# LCD_Board.net
KiCad netlist of a schematic drawn in EAGLE
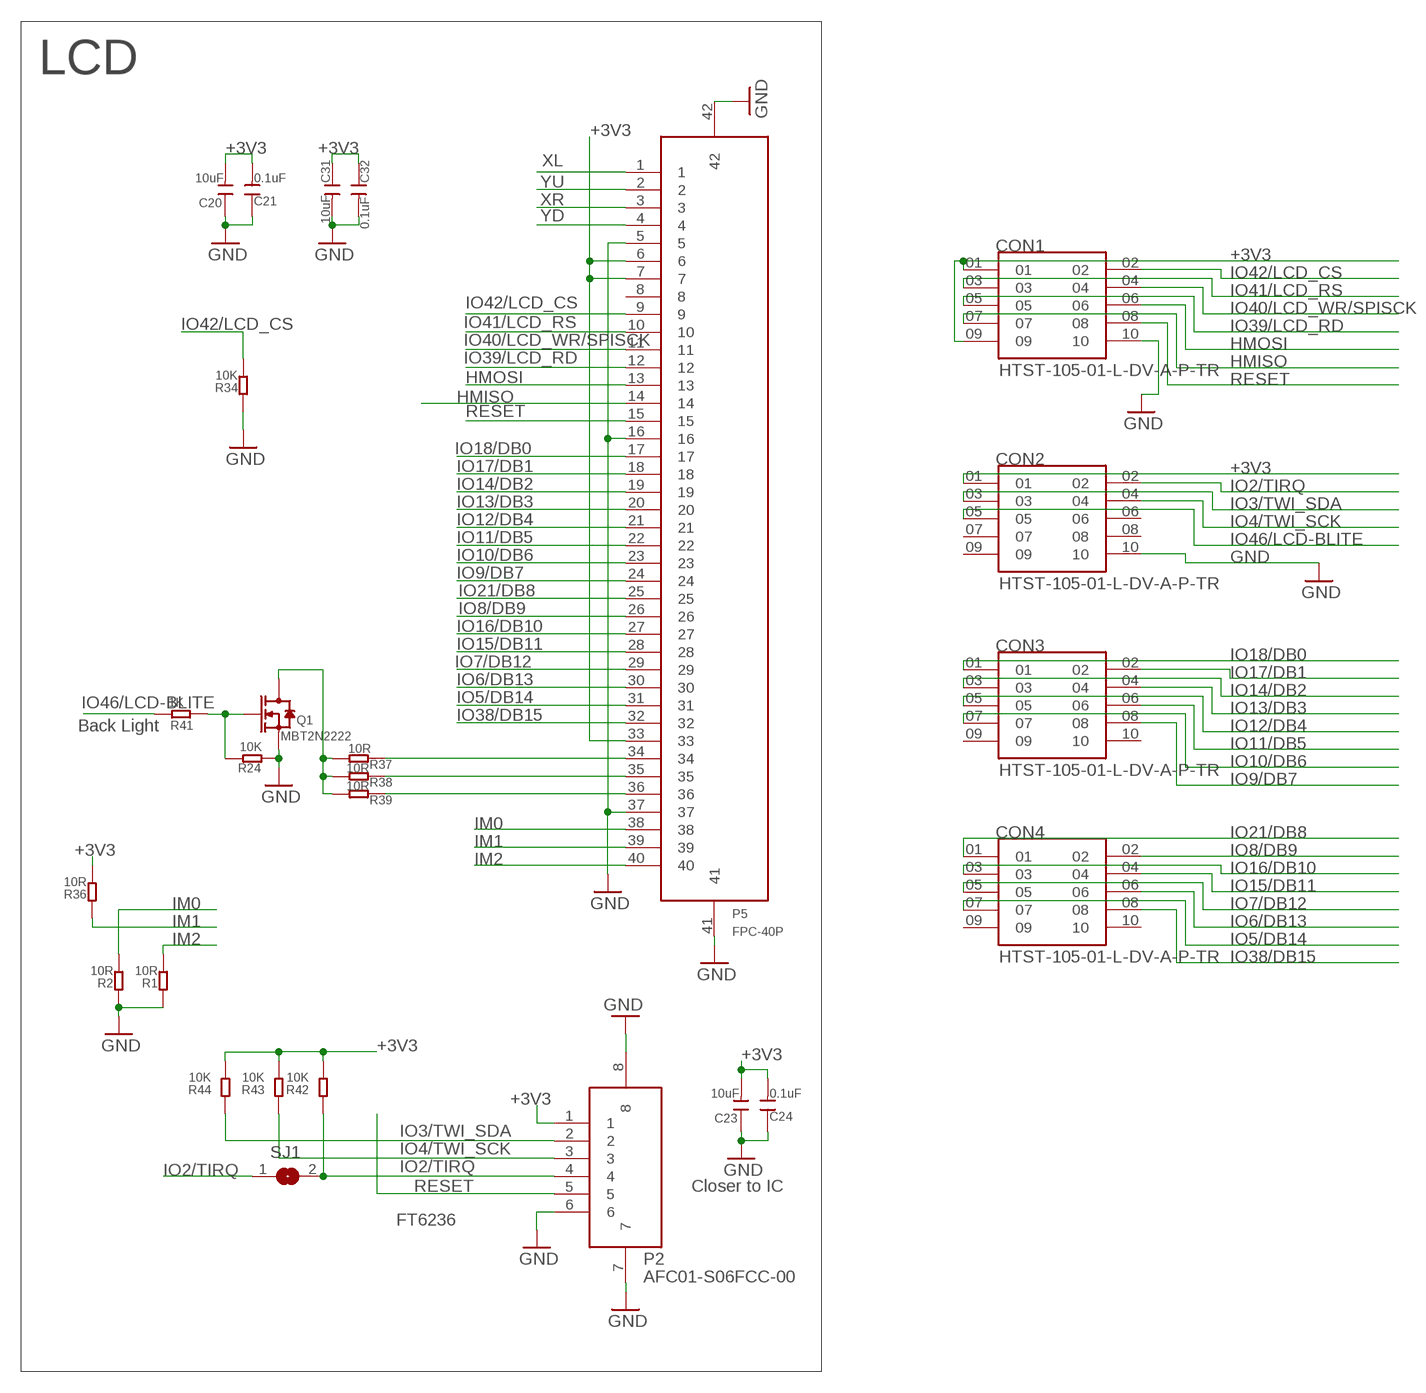
[diagram p0: schematic, sheet 1]

(export (version "E")
  (design (tool "Eeschema 10.0.6"))
  (components
    (comp (ref "C20")
      (value "10uF")
      (footprint "eagle-import:DISCRETE_C1206")
      (libsource (lib "eagle-import") (part "DISCRETE_C-1206"))
    )
    (comp (ref "C21")
      (value "0.1uF")
      (footprint "eagle-import:DISCRETE_C0603")
      (libsource (lib "eagle-import") (part "DISCRETE_C-0603"))
    )
    (comp (ref "C23")
      (value "10uF")
      (footprint "eagle-import:DISCRETE_C1206")
      (libsource (lib "eagle-import") (part "DISCRETE_C-1206"))
    )
    (comp (ref "C24")
      (value "0.1uF")
      (footprint "eagle-import:DISCRETE_C0603")
      (libsource (lib "eagle-import") (part "DISCRETE_C-0603"))
    )
    (comp (ref "C31")
      (value "10uF")
      (footprint "eagle-import:DISCRETE_C1206")
      (libsource (lib "eagle-import") (part "DISCRETE_C-1206"))
    )
    (comp (ref "C32")
      (value "0.1uF")
      (footprint "eagle-import:DISCRETE_C0603")
      (libsource (lib "eagle-import") (part "DISCRETE_C-0603"))
    )
    (comp (ref "CON1")
      (value "HTST-105-01-L-DV-A-P-TR")
      (footprint "eagle-import:SAMTEC_HTST-105-01-L-DV-A-P-TR")
      (fields (field (name "MF") "Samtec") (field (name "MP") "HTST-105-01-L-DV-A-P"))
      (libsource (lib "eagle-import") (part "HTST-105-01-L-DV-A-P-TR"))
    )
    (comp (ref "CON2")
      (value "HTST-105-01-L-DV-A-P-TR")
      (footprint "eagle-import:SAMTEC_HTST-105-01-L-DV-A-P-TR")
      (fields (field (name "MF") "Samtec") (field (name "MP") "HTST-105-01-L-DV-A-P"))
      (libsource (lib "eagle-import") (part "HTST-105-01-L-DV-A-P-TR"))
    )
    (comp (ref "CON3")
      (value "HTST-105-01-L-DV-A-P-TR")
      (footprint "eagle-import:SAMTEC_HTST-105-01-L-DV-A-P-TR")
      (fields (field (name "MF") "Samtec") (field (name "MP") "HTST-105-01-L-DV-A-P"))
      (libsource (lib "eagle-import") (part "HTST-105-01-L-DV-A-P-TR"))
    )
    (comp (ref "CON4")
      (value "HTST-105-01-L-DV-A-P-TR")
      (footprint "eagle-import:SAMTEC_HTST-105-01-L-DV-A-P-TR")
      (fields (field (name "MF") "Samtec") (field (name "MP") "HTST-105-01-L-DV-A-P"))
      (libsource (lib "eagle-import") (part "HTST-105-01-L-DV-A-P-TR"))
    )
    (comp (ref "P2")
      (value "AFC01-S06FCC-00")
      (footprint "eagle-import:SMD8-50P-740L535W")
      (libsource (lib "eagle-import") (part "AFC01-S06FCC-00"))
    )
    (comp (ref "P5")
      (value "FPC-40P")
      (footprint "eagle-import:SMD42-50P-2560L490W")
      (libsource (lib "eagle-import") (part "FPC-40P"))
    )
    (comp (ref "Q1")
      (value "MBT2N2222")
      (footprint "eagle-import:SOT23@1")
      (libsource (lib "eagle-import") (part "MOSFET-N'SOT23'"))
    )
    (comp (ref "R1")
      (value "10R")
      (footprint "eagle-import:DISCRETE_R0603")
      (libsource (lib "eagle-import") (part "DISCRETE_R-0603"))
    )
    (comp (ref "R2")
      (value "10R")
      (footprint "eagle-import:DISCRETE_R0603")
      (libsource (lib "eagle-import") (part "DISCRETE_R-0603"))
    )
    (comp (ref "R24")
      (value "10K")
      (footprint "eagle-import:DISCRETE_R0603")
      (libsource (lib "eagle-import") (part "DISCRETE_R-0603"))
    )
    (comp (ref "R34")
      (value "10K")
      (footprint "eagle-import:DISCRETE_R0603")
      (libsource (lib "eagle-import") (part "DISCRETE_R-0603"))
    )
    (comp (ref "R36")
      (value "10R")
      (footprint "eagle-import:DISCRETE_R0603")
      (libsource (lib "eagle-import") (part "DISCRETE_R-0603"))
    )
    (comp (ref "R37")
      (value "10R")
      (footprint "eagle-import:DISCRETE_R0603")
      (libsource (lib "eagle-import") (part "DISCRETE_R-0603"))
    )
    (comp (ref "R38")
      (value "10R")
      (footprint "eagle-import:DISCRETE_R0603")
      (libsource (lib "eagle-import") (part "DISCRETE_R-0603"))
    )
    (comp (ref "R39")
      (value "10R")
      (footprint "eagle-import:DISCRETE_R0603")
      (libsource (lib "eagle-import") (part "DISCRETE_R-0603"))
    )
    (comp (ref "R41")
      (value "1K")
      (footprint "eagle-import:DISCRETE_R0603")
      (libsource (lib "eagle-import") (part "DISCRETE_R-0603"))
    )
    (comp (ref "R42")
      (value "10K")
      (footprint "eagle-import:DISCRETE_R0603")
      (libsource (lib "eagle-import") (part "DISCRETE_R-0603"))
    )
    (comp (ref "R43")
      (value "10K")
      (footprint "eagle-import:DISCRETE_R0603")
      (libsource (lib "eagle-import") (part "DISCRETE_R-0603"))
    )
    (comp (ref "R44")
      (value "10K")
      (footprint "eagle-import:DISCRETE_R0603")
      (libsource (lib "eagle-import") (part "DISCRETE_R-0603"))
    )
    (comp (ref "SJ1") (value "SJ") (footprint "eagle-import:SJ") (libsource (lib "eagle-import") (part "SJ")))
  )
  (nets
    (net (code "1") (name "/+3V3") (class "Default")
      (node (ref "C20") (pin "2") (pinfunction "2_2") (pintype "passive"))
      (node (ref "C21") (pin "2") (pinfunction "2_2") (pintype "passive"))
      (node (ref "C23") (pin "2") (pinfunction "2_2") (pintype "passive"))
      (node (ref "C24") (pin "2") (pinfunction "2_2") (pintype "passive"))
      (node (ref "C31") (pin "1") (pinfunction "1_1") (pintype "passive"))
      (node (ref "C32") (pin "1") (pinfunction "1_1") (pintype "passive"))
      (node (ref "CON1") (pin "01") (pinfunction "01_01") (pintype "passive"))
      (node (ref "CON1") (pin "09") (pinfunction "09_09") (pintype "passive"))
      (node (ref "CON2") (pin "01") (pinfunction "01_01") (pintype "passive"))
      (node (ref "P2") (pin "1") (pinfunction "1_1") (pintype "bidirectional"))
      (node (ref "P5") (pin "33") (pinfunction "33_33") (pintype "bidirectional"))
      (node (ref "P5") (pin "6") (pinfunction "6_6") (pintype "bidirectional"))
      (node (ref "P5") (pin "7") (pinfunction "7_7") (pintype "bidirectional"))
      (node (ref "R36") (pin "2") (pinfunction "2_2") (pintype "passive"))
      (node (ref "R42") (pin "2") (pinfunction "2_2") (pintype "passive"))
      (node (ref "R43") (pin "2") (pinfunction "2_2") (pintype "passive"))
      (node (ref "R44") (pin "2") (pinfunction "2_2") (pintype "passive"))
    )
    (net (code "2") (name "/HMISO") (class "Default")
      (node (ref "CON1") (pin "07") (pinfunction "07_07") (pintype "passive"))
      (node (ref "P5") (pin "14") (pinfunction "14_14") (pintype "bidirectional"))
    )
    (net (code "3") (name "/HMOSI") (class "Default")
      (node (ref "CON1") (pin "06") (pinfunction "06_06") (pintype "passive"))
      (node (ref "P5") (pin "13") (pinfunction "13_13") (pintype "bidirectional"))
    )
    (net (code "4") (name "/IM0") (class "Default")
      (node (ref "P5") (pin "38") (pinfunction "38_38") (pintype "bidirectional"))
      (node (ref "R2") (pin "2") (pinfunction "2_2") (pintype "passive"))
    )
    (net (code "5") (name "/IM1") (class "Default")
      (node (ref "P5") (pin "39") (pinfunction "39_39") (pintype "bidirectional"))
      (node (ref "R36") (pin "1") (pinfunction "1_1") (pintype "passive"))
    )
    (net (code "6") (name "/IM2") (class "Default")
      (node (ref "P5") (pin "40") (pinfunction "40_40") (pintype "bidirectional"))
      (node (ref "R1") (pin "2") (pinfunction "2_2") (pintype "passive"))
    )
    (net (code "7") (name "/IO2{slash}TIRQ") (class "Default")
      (node (ref "CON2") (pin "02") (pinfunction "02_02") (pintype "passive"))
      (node (ref "P2") (pin "4") (pinfunction "4_4") (pintype "bidirectional"))
      (node (ref "R42") (pin "1") (pinfunction "1_1") (pintype "passive"))
      (node (ref "SJ1") (pin "1") (pinfunction "1_1") (pintype "passive"))
      (node (ref "SJ1") (pin "2") (pinfunction "2_2") (pintype "passive"))
    )
    (net (code "8") (name "/IO3{slash}TWI_SDA") (class "Default")
      (node (ref "CON2") (pin "03") (pinfunction "03_03") (pintype "passive"))
      (node (ref "P2") (pin "2") (pinfunction "2_2") (pintype "bidirectional"))
      (node (ref "R44") (pin "1") (pinfunction "1_1") (pintype "passive"))
    )
    (net (code "9") (name "/IO4{slash}TWI_SCK") (class "Default")
      (node (ref "CON2") (pin "04") (pinfunction "04_04") (pintype "passive"))
      (node (ref "P2") (pin "3") (pinfunction "3_3") (pintype "bidirectional"))
      (node (ref "R43") (pin "1") (pinfunction "1_1") (pintype "passive"))
    )
    (net (code "10") (name "/IO5{slash}DB14") (class "Default")
      (node (ref "CON4") (pin "07") (pinfunction "07_07") (pintype "passive"))
      (node (ref "P5") (pin "31") (pinfunction "31_31") (pintype "bidirectional"))
    )
    (net (code "11") (name "/IO6{slash}DB13") (class "Default")
      (node (ref "CON4") (pin "06") (pinfunction "06_06") (pintype "passive"))
      (node (ref "P5") (pin "30") (pinfunction "30_30") (pintype "bidirectional"))
    )
    (net (code "12") (name "/IO7{slash}DB12") (class "Default")
      (node (ref "CON4") (pin "05") (pinfunction "05_05") (pintype "passive"))
      (node (ref "P5") (pin "29") (pinfunction "29_29") (pintype "bidirectional"))
    )
    (net (code "13") (name "/IO8{slash}DB9") (class "Default")
      (node (ref "CON4") (pin "02") (pinfunction "02_02") (pintype "passive"))
      (node (ref "P5") (pin "26") (pinfunction "26_26") (pintype "bidirectional"))
    )
    (net (code "14") (name "/IO9{slash}DB7") (class "Default")
      (node (ref "CON3") (pin "08") (pinfunction "08_08") (pintype "passive"))
      (node (ref "P5") (pin "24") (pinfunction "24_24") (pintype "bidirectional"))
    )
    (net (code "15") (name "/IO10{slash}DB6") (class "Default")
      (node (ref "CON3") (pin "07") (pinfunction "07_07") (pintype "passive"))
      (node (ref "P5") (pin "23") (pinfunction "23_23") (pintype "bidirectional"))
    )
    (net (code "16") (name "/IO11{slash}DB5") (class "Default")
      (node (ref "CON3") (pin "06") (pinfunction "06_06") (pintype "passive"))
      (node (ref "P5") (pin "22") (pinfunction "22_22") (pintype "bidirectional"))
    )
    (net (code "17") (name "/IO12{slash}DB4") (class "Default")
      (node (ref "CON3") (pin "05") (pinfunction "05_05") (pintype "passive"))
      (node (ref "P5") (pin "21") (pinfunction "21_21") (pintype "bidirectional"))
    )
    (net (code "18") (name "/IO13{slash}DB3") (class "Default")
      (node (ref "CON3") (pin "04") (pinfunction "04_04") (pintype "passive"))
      (node (ref "P5") (pin "20") (pinfunction "20_20") (pintype "bidirectional"))
    )
    (net (code "19") (name "/IO14{slash}DB2") (class "Default")
      (node (ref "CON3") (pin "03") (pinfunction "03_03") (pintype "passive"))
      (node (ref "P5") (pin "19") (pinfunction "19_19") (pintype "bidirectional"))
    )
    (net (code "20") (name "/IO15{slash}DB11") (class "Default")
      (node (ref "CON4") (pin "04") (pinfunction "04_04") (pintype "passive"))
      (node (ref "P5") (pin "28") (pinfunction "28_28") (pintype "bidirectional"))
    )
    (net (code "21") (name "/IO16{slash}DB10") (class "Default")
      (node (ref "CON4") (pin "03") (pinfunction "03_03") (pintype "passive"))
      (node (ref "P5") (pin "27") (pinfunction "27_27") (pintype "bidirectional"))
    )
    (net (code "22") (name "/IO17{slash}DB1") (class "Default")
      (node (ref "CON3") (pin "02") (pinfunction "02_02") (pintype "passive"))
      (node (ref "P5") (pin "18") (pinfunction "18_18") (pintype "bidirectional"))
    )
    (net (code "23") (name "/IO18{slash}DB0") (class "Default")
      (node (ref "CON3") (pin "01") (pinfunction "01_01") (pintype "passive"))
      (node (ref "P5") (pin "17") (pinfunction "17_17") (pintype "bidirectional"))
    )
    (net (code "24") (name "/IO21{slash}DB8") (class "Default")
      (node (ref "CON4") (pin "01") (pinfunction "01_01") (pintype "passive"))
      (node (ref "P5") (pin "25") (pinfunction "25_25") (pintype "bidirectional"))
    )
    (net (code "25") (name "/IO38{slash}DB15") (class "Default")
      (node (ref "CON4") (pin "08") (pinfunction "08_08") (pintype "passive"))
      (node (ref "P5") (pin "32") (pinfunction "32_32") (pintype "bidirectional"))
    )
    (net (code "26") (name "/IO39{slash}LCD_RD") (class "Default")
      (node (ref "CON1") (pin "05") (pinfunction "05_05") (pintype "passive"))
      (node (ref "P5") (pin "12") (pinfunction "12_12") (pintype "bidirectional"))
    )
    (net (code "27") (name "/IO40{slash}LCD_WR{slash}SPISCK") (class "Default")
      (node (ref "CON1") (pin "04") (pinfunction "04_04") (pintype "passive"))
      (node (ref "P5") (pin "11") (pinfunction "11_11") (pintype "bidirectional"))
    )
    (net (code "28") (name "/IO41{slash}LCD_RS") (class "Default")
      (node (ref "CON1") (pin "03") (pinfunction "03_03") (pintype "passive"))
      (node (ref "P5") (pin "10") (pinfunction "10_10") (pintype "bidirectional"))
    )
    (net (code "29") (name "/IO42{slash}LCD_CS") (class "Default")
      (node (ref "CON1") (pin "02") (pinfunction "02_02") (pintype "passive"))
      (node (ref "P5") (pin "9") (pinfunction "9_9") (pintype "bidirectional"))
      (node (ref "R34") (pin "2") (pinfunction "2_2") (pintype "passive"))
    )
    (net (code "30") (name "/IO46{slash}LCD-BLITE") (class "Default")
      (node (ref "CON2") (pin "05") (pinfunction "05_05") (pintype "passive"))
      (node (ref "R41") (pin "2") (pinfunction "2_2") (pintype "passive"))
    )
    (net (code "31") (name "/RESET") (class "Default")
      (node (ref "CON1") (pin "08") (pinfunction "08_08") (pintype "passive"))
      (node (ref "P2") (pin "5") (pinfunction "5_5") (pintype "bidirectional"))
      (node (ref "P5") (pin "15") (pinfunction "15_15") (pintype "bidirectional"))
    )
    (net (code "32") (name "/XL") (class "Default")
      (node (ref "P5") (pin "1") (pinfunction "1_1") (pintype "bidirectional"))
    )
    (net (code "33") (name "/XR") (class "Default")
      (node (ref "P5") (pin "3") (pinfunction "3_3") (pintype "bidirectional"))
    )
    (net (code "34") (name "/YD") (class "Default")
      (node (ref "P5") (pin "4") (pinfunction "4_4") (pintype "bidirectional"))
    )
    (net (code "35") (name "/YU") (class "Default")
      (node (ref "P5") (pin "2") (pinfunction "2_2") (pintype "bidirectional"))
    )
    (net (code "36") (name "GND") (class "Default")
      (node (ref "C20") (pin "1") (pinfunction "1_1") (pintype "passive"))
      (node (ref "C21") (pin "1") (pinfunction "1_1") (pintype "passive"))
      (node (ref "C23") (pin "1") (pinfunction "1_1") (pintype "passive"))
      (node (ref "C24") (pin "1") (pinfunction "1_1") (pintype "passive"))
      (node (ref "C31") (pin "2") (pinfunction "2_2") (pintype "passive"))
      (node (ref "C32") (pin "2") (pinfunction "2_2") (pintype "passive"))
      (node (ref "CON1") (pin "10") (pinfunction "10_10") (pintype "passive"))
      (node (ref "CON2") (pin "10") (pinfunction "10_10") (pintype "passive"))
      (node (ref "P2") (pin "6") (pinfunction "6_6") (pintype "bidirectional"))
      (node (ref "P2") (pin "7") (pinfunction "7_7") (pintype "bidirectional"))
      (node (ref "P2") (pin "8") (pinfunction "8_8") (pintype "bidirectional"))
      (node (ref "P5") (pin "16") (pinfunction "16_16") (pintype "bidirectional"))
      (node (ref "P5") (pin "37") (pinfunction "37_37") (pintype "bidirectional"))
      (node (ref "P5") (pin "41") (pinfunction "41_41") (pintype "bidirectional"))
      (node (ref "P5") (pin "42") (pinfunction "42_42") (pintype "bidirectional"))
      (node (ref "P5") (pin "5") (pinfunction "5_5") (pintype "bidirectional"))
      (node (ref "Q1") (pin "2") (pinfunction "S_2") (pintype "passive"))
      (node (ref "R1") (pin "1") (pinfunction "1_1") (pintype "passive"))
      (node (ref "R2") (pin "1") (pinfunction "1_1") (pintype "passive"))
      (node (ref "R24") (pin "1") (pinfunction "1_1") (pintype "passive"))
      (node (ref "R34") (pin "1") (pinfunction "1_1") (pintype "passive"))
    )
    (net (code "37") (name "Net-(P5-Pad34)") (class "Default")
      (node (ref "P5") (pin "34") (pinfunction "34_34") (pintype "bidirectional"))
      (node (ref "R37") (pin "1") (pinfunction "1_1") (pintype "passive"))
    )
    (net (code "38") (name "Net-(P5-Pad35)") (class "Default")
      (node (ref "P5") (pin "35") (pinfunction "35_35") (pintype "bidirectional"))
      (node (ref "R38") (pin "1") (pinfunction "1_1") (pintype "passive"))
    )
    (net (code "39") (name "Net-(P5-Pad36)") (class "Default")
      (node (ref "P5") (pin "36") (pinfunction "36_36") (pintype "bidirectional"))
      (node (ref "R39") (pin "1") (pinfunction "1_1") (pintype "passive"))
    )
    (net (code "40") (name "Net-(Q1-D)") (class "Default")
      (node (ref "Q1") (pin "3") (pinfunction "D_3") (pintype "passive"))
      (node (ref "R37") (pin "2") (pinfunction "2_2") (pintype "passive"))
      (node (ref "R38") (pin "2") (pinfunction "2_2") (pintype "passive"))
      (node (ref "R39") (pin "2") (pinfunction "2_2") (pintype "passive"))
    )
    (net (code "41") (name "Net-(Q1-G)") (class "Default")
      (node (ref "Q1") (pin "1") (pinfunction "G_1") (pintype "passive"))
      (node (ref "R24") (pin "2") (pinfunction "2_2") (pintype "passive"))
      (node (ref "R41") (pin "1") (pinfunction "1_1") (pintype "passive"))
    )
    (net (code "42") (name "unconnected-(CON2-Pad06)") (class "Default")
      (node (ref "CON2") (pin "06") (pinfunction "06_06") (pintype "passive"))
    )
    (net (code "43") (name "unconnected-(CON2-Pad07)") (class "Default")
      (node (ref "CON2") (pin "07") (pinfunction "07_07") (pintype "passive"))
    )
    (net (code "44") (name "unconnected-(CON2-Pad08)") (class "Default")
      (node (ref "CON2") (pin "08") (pinfunction "08_08") (pintype "passive"))
    )
    (net (code "45") (name "unconnected-(CON2-Pad09)") (class "Default")
      (node (ref "CON2") (pin "09") (pinfunction "09_09") (pintype "passive"))
    )
    (net (code "46") (name "unconnected-(CON3-Pad09)") (class "Default")
      (node (ref "CON3") (pin "09") (pinfunction "09_09") (pintype "passive"))
    )
    (net (code "47") (name "unconnected-(CON3-Pad10)") (class "Default")
      (node (ref "CON3") (pin "10") (pinfunction "10_10") (pintype "passive"))
    )
    (net (code "48") (name "unconnected-(CON4-Pad09)") (class "Default")
      (node (ref "CON4") (pin "09") (pinfunction "09_09") (pintype "passive"))
    )
    (net (code "49") (name "unconnected-(CON4-Pad10)") (class "Default")
      (node (ref "CON4") (pin "10") (pinfunction "10_10") (pintype "passive"))
    )
    (net (code "50") (name "unconnected-(P5-Pad8)") (class "Default")
      (node (ref "P5") (pin "8") (pinfunction "8_8") (pintype "bidirectional"))
    )
  )
)
